# Dartautomat.net
KiCad netlist of a schematic drawn in EAGLE
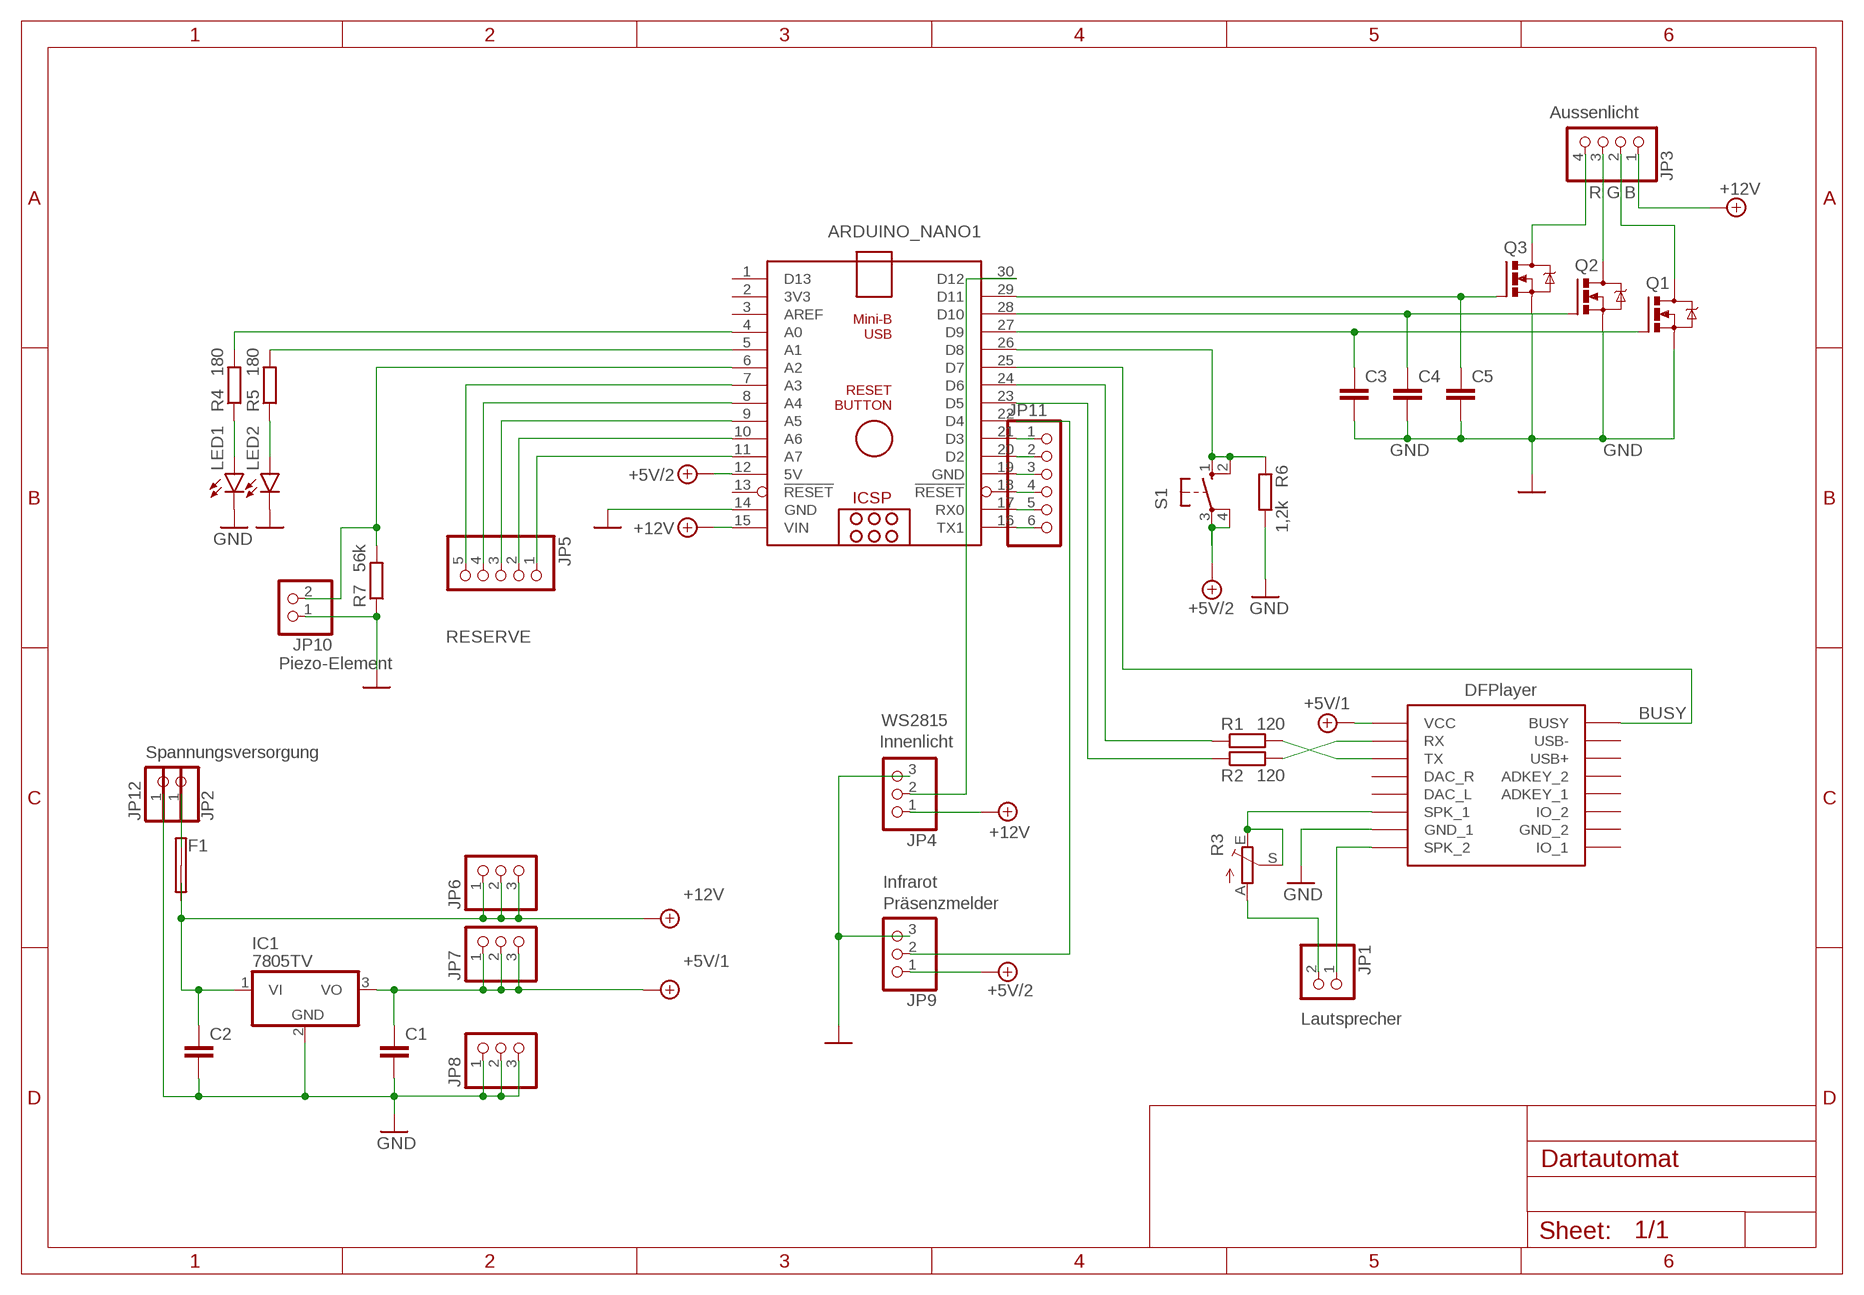
[diagram p0: schematic, sheet 1]

(export (version "E")
  (design (tool "Eeschema 10.0.6"))
  (components
    (comp (ref "ARDUINO_NANO1")
      (value "ARDUINO_NANO")
      (footprint "eagle-import:ARDUINO_NANO")
      (libsource (lib "eagle-import") (part "ARDUINO_NANO"))
    )
    (comp (ref "C1")
      (value "C-EU050-045X075")
      (footprint "eagle-import:C050-045X075")
      (libsource (lib "eagle-import") (part "C-EU050-045X075"))
    )
    (comp (ref "C2")
      (value "C-EU050-045X075")
      (footprint "eagle-import:C050-045X075")
      (libsource (lib "eagle-import") (part "C-EU050-045X075"))
    )
    (comp (ref "C3")
      (value "C-EU050-045X075")
      (footprint "eagle-import:C050-045X075")
      (libsource (lib "eagle-import") (part "C-EU050-045X075"))
    )
    (comp (ref "C4")
      (value "C-EU050-045X075")
      (footprint "eagle-import:C050-045X075")
      (libsource (lib "eagle-import") (part "C-EU050-045X075"))
    )
    (comp (ref "C5")
      (value "C-EU050-045X075")
      (footprint "eagle-import:C050-045X075")
      (libsource (lib "eagle-import") (part "C-EU050-045X075"))
    )
    (comp (ref "F1")
      (value "SHK20L")
      (footprint "eagle-import:SHK20L")
      (libsource (lib "eagle-import") (part "SHK20L"))
    )
    (comp (ref "IC1")
      (value "7805TV")
      (footprint "eagle-import:TO220V")
      (libsource (lib "eagle-import") (part "78TV05"))
    )
    (comp (ref "JP1")
      (value "PINHD-1X2")
      (footprint "eagle-import:1X02")
      (libsource (lib "eagle-import") (part "PINHD-1X2"))
    )
    (comp (ref "JP2")
      (value "PINHD-1X1")
      (footprint "eagle-import:1X01")
      (libsource (lib "eagle-import") (part "PINHD-1X1"))
    )
    (comp (ref "JP3")
      (value "PINHD-1X4")
      (footprint "eagle-import:1X04")
      (libsource (lib "eagle-import") (part "PINHD-1X4"))
    )
    (comp (ref "JP4")
      (value "PINHD-1X3")
      (footprint "eagle-import:1X03")
      (libsource (lib "eagle-import") (part "PINHD-1X3"))
    )
    (comp (ref "JP5")
      (value "PINHD-1X5")
      (footprint "eagle-import:1X05")
      (libsource (lib "eagle-import") (part "PINHD-1X5"))
    )
    (comp (ref "JP6")
      (value "PINHD-1X3")
      (footprint "eagle-import:1X03")
      (libsource (lib "eagle-import") (part "PINHD-1X3"))
    )
    (comp (ref "JP7")
      (value "PINHD-1X3")
      (footprint "eagle-import:1X03")
      (libsource (lib "eagle-import") (part "PINHD-1X3"))
    )
    (comp (ref "JP8")
      (value "PINHD-1X3")
      (footprint "eagle-import:1X03")
      (libsource (lib "eagle-import") (part "PINHD-1X3"))
    )
    (comp (ref "JP9")
      (value "PINHD-1X3")
      (footprint "eagle-import:1X03")
      (libsource (lib "eagle-import") (part "PINHD-1X3"))
    )
    (comp (ref "JP10")
      (value "PINHD-1X2")
      (footprint "eagle-import:1X02")
      (libsource (lib "eagle-import") (part "PINHD-1X2"))
    )
    (comp (ref "JP11")
      (value "PINHD-1X6")
      (footprint "eagle-import:1X06")
      (libsource (lib "eagle-import") (part "PINHD-1X6"))
    )
    (comp (ref "JP12")
      (value "PINHD-1X1")
      (footprint "eagle-import:1X01")
      (libsource (lib "eagle-import") (part "PINHD-1X1"))
    )
    (comp (ref "LED1")
      (value "LED3MM")
      (footprint "eagle-import:LED3MM")
      (libsource (lib "eagle-import") (part "LED3MM"))
    )
    (comp (ref "LED2")
      (value "LED3MM")
      (footprint "eagle-import:LED3MM")
      (libsource (lib "eagle-import") (part "LED3MM"))
    )
    (comp (ref "Q1")
      (value "IRLZ44ZNEU")
      (footprint "eagle-import:TO220BV")
      (libsource (lib "eagle-import") (part "IRLZ44ZNEU"))
    )
    (comp (ref "Q2")
      (value "IRLZ44ZNEU")
      (footprint "eagle-import:TO220BV")
      (libsource (lib "eagle-import") (part "IRLZ44ZNEU"))
    )
    (comp (ref "Q3")
      (value "IRLZ44ZNEU")
      (footprint "eagle-import:TO220BV")
      (libsource (lib "eagle-import") (part "IRLZ44ZNEU"))
    )
    (comp (ref "R1")
      (value "120")
      (footprint "eagle-import:0207_10")
      (libsource (lib "eagle-import") (part "R-EU_0207/10"))
    )
    (comp (ref "R2")
      (value "120")
      (footprint "eagle-import:0207_10")
      (libsource (lib "eagle-import") (part "R-EU_0207/10"))
    )
    (comp (ref "R3")
      (value "TRIM_EU-CA6H")
      (footprint "eagle-import:CA6H")
      (libsource (lib "eagle-import") (part "TRIM_EU-CA6H"))
    )
    (comp (ref "R4")
      (value "180")
      (footprint "eagle-import:0207_12")
      (libsource (lib "eagle-import") (part "R-EU_0207/12"))
    )
    (comp (ref "R5")
      (value "180")
      (footprint "eagle-import:0207_12")
      (libsource (lib "eagle-import") (part "R-EU_0207/12"))
    )
    (comp (ref "R6")
      (value "1,2k")
      (footprint "eagle-import:0207_12")
      (libsource (lib "eagle-import") (part "R-EU_0207/12"))
    )
    (comp (ref "R7")
      (value "56k")
      (footprint "eagle-import:0207_12")
      (libsource (lib "eagle-import") (part "R-EU_0207/12"))
    )
    (comp (ref "S1")
      (value "10-XX")
      (footprint "eagle-import:B3F-10XX")
      (fields (field (name "MPN") "B3F-1000"))
      (libsource (lib "eagle-import") (part "10-XX"))
    )
    (comp (ref "U$1")
      (value "DFPLAYER")
      (footprint "eagle-import:DFPLAYER")
      (libsource (lib "eagle-import") (part "DFPLAYER"))
    )
  )
  (nets
    (net (code "1") (name "+5V{slash}1") (class "Default")
      (node (ref "C1") (pin "1") (pinfunction "1_1") (pintype "passive"))
      (node (ref "IC1") (pin "3") (pinfunction "VO_3") (pintype "passive"))
      (node (ref "JP7") (pin "1") (pinfunction "1_1") (pintype "passive"))
      (node (ref "JP7") (pin "2") (pinfunction "2_2") (pintype "passive"))
      (node (ref "JP7") (pin "3") (pinfunction "3_3") (pintype "passive"))
      (node (ref "U$1") (pin "VCC") (pinfunction "VCC_VCC") (pintype "bidirectional"))
    )
    (net (code "2") (name "+5V{slash}2") (class "Default")
      (node (ref "ARDUINO_NANO1") (pin "12") (pinfunction "5V_12") (pintype "power_in"))
      (node (ref "JP9") (pin "1") (pinfunction "1_1") (pintype "passive"))
      (node (ref "S1") (pin "3") (pinfunction "P_3") (pintype "passive"))
      (node (ref "S1") (pin "4") (pinfunction "P1_4") (pintype "passive"))
    )
    (net (code "3") (name "+12V") (class "Default")
      (node (ref "ARDUINO_NANO1") (pin "15") (pinfunction "VIN_15") (pintype "power_in"))
      (node (ref "C2") (pin "1") (pinfunction "1_1") (pintype "passive"))
      (node (ref "F1") (pin "1A") (pinfunction "1A_1A") (pintype "passive"))
      (node (ref "F1") (pin "1B") (pinfunction "1B_1B") (pintype "passive"))
      (node (ref "IC1") (pin "1") (pinfunction "VI_1") (pintype "input"))
      (node (ref "JP3") (pin "1") (pinfunction "1_1") (pintype "passive"))
      (node (ref "JP4") (pin "1") (pinfunction "1_1") (pintype "passive"))
      (node (ref "JP6") (pin "1") (pinfunction "1_1") (pintype "passive"))
      (node (ref "JP6") (pin "2") (pinfunction "2_2") (pintype "passive"))
      (node (ref "JP6") (pin "3") (pinfunction "3_3") (pintype "passive"))
    )
    (net (code "4") (name "/BUSY") (class "Default")
      (node (ref "ARDUINO_NANO1") (pin "25") (pinfunction "D7_25") (pintype "bidirectional"))
      (node (ref "U$1") (pin "BUSY") (pinfunction "BUSY_BUSY") (pintype "bidirectional"))
    )
    (net (code "5") (name "GND") (class "Default")
      (node (ref "ARDUINO_NANO1") (pin "14") (pinfunction "GND_14") (pintype "power_in"))
      (node (ref "C1") (pin "2") (pinfunction "2_2") (pintype "passive"))
      (node (ref "C2") (pin "2") (pinfunction "2_2") (pintype "passive"))
      (node (ref "C3") (pin "2") (pinfunction "2_2") (pintype "passive"))
      (node (ref "C4") (pin "2") (pinfunction "2_2") (pintype "passive"))
      (node (ref "C5") (pin "2") (pinfunction "2_2") (pintype "passive"))
      (node (ref "IC1") (pin "2") (pinfunction "GND_2") (pintype "passive"))
      (node (ref "JP10") (pin "1") (pinfunction "1_1") (pintype "passive"))
      (node (ref "JP12") (pin "1") (pinfunction "1_1") (pintype "passive"))
      (node (ref "JP4") (pin "3") (pinfunction "3_3") (pintype "passive"))
      (node (ref "JP8") (pin "1") (pinfunction "1_1") (pintype "passive"))
      (node (ref "JP8") (pin "2") (pinfunction "2_2") (pintype "passive"))
      (node (ref "JP8") (pin "3") (pinfunction "3_3") (pintype "passive"))
      (node (ref "JP9") (pin "3") (pinfunction "3_3") (pintype "passive"))
      (node (ref "LED1") (pin "K") (pinfunction "C_K") (pintype "passive"))
      (node (ref "LED2") (pin "K") (pinfunction "C_K") (pintype "passive"))
      (node (ref "Q1") (pin "S") (pinfunction "S_S") (pintype "passive"))
      (node (ref "Q2") (pin "S") (pinfunction "S_S") (pintype "passive"))
      (node (ref "Q3") (pin "S") (pinfunction "S_S") (pintype "passive"))
      (node (ref "R6") (pin "2") (pinfunction "2_2") (pintype "passive"))
      (node (ref "R7") (pin "1") (pinfunction "1_1") (pintype "passive"))
      (node (ref "U$1") (pin "GND_1") (pinfunction "GND_1_GND_1") (pintype "bidirectional"))
    )
    (net (code "6") (name "Net-(ARDUINO_NANO1-A0)") (class "Default")
      (node (ref "ARDUINO_NANO1") (pin "4") (pinfunction "A0_4") (pintype "bidirectional"))
      (node (ref "R4") (pin "2") (pinfunction "2_2") (pintype "passive"))
    )
    (net (code "7") (name "Net-(ARDUINO_NANO1-A1)") (class "Default")
      (node (ref "ARDUINO_NANO1") (pin "5") (pinfunction "A1_5") (pintype "bidirectional"))
      (node (ref "R5") (pin "2") (pinfunction "2_2") (pintype "passive"))
    )
    (net (code "8") (name "Net-(ARDUINO_NANO1-A2)") (class "Default")
      (node (ref "ARDUINO_NANO1") (pin "6") (pinfunction "A2_6") (pintype "bidirectional"))
      (node (ref "JP10") (pin "2") (pinfunction "2_2") (pintype "passive"))
      (node (ref "R7") (pin "2") (pinfunction "2_2") (pintype "passive"))
    )
    (net (code "9") (name "Net-(ARDUINO_NANO1-A3)") (class "Default")
      (node (ref "ARDUINO_NANO1") (pin "7") (pinfunction "A3_7") (pintype "bidirectional"))
      (node (ref "JP5") (pin "5") (pinfunction "5_5") (pintype "passive"))
    )
    (net (code "10") (name "Net-(ARDUINO_NANO1-A4)") (class "Default")
      (node (ref "ARDUINO_NANO1") (pin "8") (pinfunction "A4_8") (pintype "bidirectional"))
      (node (ref "JP5") (pin "4") (pinfunction "4_4") (pintype "passive"))
    )
    (net (code "11") (name "Net-(ARDUINO_NANO1-A5)") (class "Default")
      (node (ref "ARDUINO_NANO1") (pin "9") (pinfunction "A5_9") (pintype "bidirectional"))
      (node (ref "JP5") (pin "3") (pinfunction "3_3") (pintype "passive"))
    )
    (net (code "12") (name "Net-(ARDUINO_NANO1-A6)") (class "Default")
      (node (ref "ARDUINO_NANO1") (pin "10") (pinfunction "A6_10") (pintype "bidirectional"))
      (node (ref "JP5") (pin "2") (pinfunction "2_2") (pintype "passive"))
    )
    (net (code "13") (name "Net-(ARDUINO_NANO1-A7)") (class "Default")
      (node (ref "ARDUINO_NANO1") (pin "11") (pinfunction "A7_11") (pintype "bidirectional"))
      (node (ref "JP5") (pin "1") (pinfunction "1_1") (pintype "passive"))
    )
    (net (code "14") (name "Net-(ARDUINO_NANO1-D2)") (class "Default")
      (node (ref "ARDUINO_NANO1") (pin "20") (pinfunction "D2_20") (pintype "bidirectional"))
      (node (ref "JP11") (pin "2") (pinfunction "2_2") (pintype "passive"))
    )
    (net (code "15") (name "Net-(ARDUINO_NANO1-D3)") (class "Default")
      (node (ref "ARDUINO_NANO1") (pin "21") (pinfunction "D3_21") (pintype "bidirectional"))
      (node (ref "JP11") (pin "1") (pinfunction "1_1") (pintype "passive"))
    )
    (net (code "16") (name "Net-(ARDUINO_NANO1-D4)") (class "Default")
      (node (ref "ARDUINO_NANO1") (pin "22") (pinfunction "D4_22") (pintype "bidirectional"))
      (node (ref "JP9") (pin "2") (pinfunction "2_2") (pintype "passive"))
    )
    (net (code "17") (name "Net-(ARDUINO_NANO1-D5)") (class "Default")
      (node (ref "ARDUINO_NANO1") (pin "23") (pinfunction "D5_23") (pintype "bidirectional"))
      (node (ref "R2") (pin "1") (pinfunction "1_1") (pintype "passive"))
    )
    (net (code "18") (name "Net-(ARDUINO_NANO1-D6)") (class "Default")
      (node (ref "ARDUINO_NANO1") (pin "24") (pinfunction "D6_24") (pintype "bidirectional"))
      (node (ref "R1") (pin "1") (pinfunction "1_1") (pintype "passive"))
    )
    (net (code "19") (name "Net-(ARDUINO_NANO1-D8)") (class "Default")
      (node (ref "ARDUINO_NANO1") (pin "26") (pinfunction "D8_26") (pintype "bidirectional"))
      (node (ref "R6") (pin "1") (pinfunction "1_1") (pintype "passive"))
      (node (ref "S1") (pin "1") (pinfunction "S_1") (pintype "passive"))
      (node (ref "S1") (pin "2") (pinfunction "S1_2") (pintype "passive"))
    )
    (net (code "20") (name "Net-(ARDUINO_NANO1-D9)") (class "Default")
      (node (ref "ARDUINO_NANO1") (pin "27") (pinfunction "D9_27") (pintype "bidirectional"))
      (node (ref "C3") (pin "1") (pinfunction "1_1") (pintype "passive"))
      (node (ref "Q1") (pin "G") (pinfunction "G_G") (pintype "passive"))
    )
    (net (code "21") (name "Net-(ARDUINO_NANO1-D10)") (class "Default")
      (node (ref "ARDUINO_NANO1") (pin "28") (pinfunction "D10_28") (pintype "bidirectional"))
      (node (ref "C4") (pin "1") (pinfunction "1_1") (pintype "passive"))
      (node (ref "Q2") (pin "G") (pinfunction "G_G") (pintype "passive"))
    )
    (net (code "22") (name "Net-(ARDUINO_NANO1-D11)") (class "Default")
      (node (ref "ARDUINO_NANO1") (pin "29") (pinfunction "D11_29") (pintype "bidirectional"))
      (node (ref "C5") (pin "1") (pinfunction "1_1") (pintype "passive"))
      (node (ref "Q3") (pin "G") (pinfunction "G_G") (pintype "passive"))
    )
    (net (code "23") (name "Net-(ARDUINO_NANO1-D12)") (class "Default")
      (node (ref "ARDUINO_NANO1") (pin "30") (pinfunction "D12_30") (pintype "bidirectional"))
      (node (ref "JP4") (pin "2") (pinfunction "2_2") (pintype "passive"))
    )
    (net (code "24") (name "Net-(ARDUINO_NANO1-GND-Pad19)") (class "Default")
      (node (ref "ARDUINO_NANO1") (pin "19") (pinfunction "GND_19") (pintype "power_in"))
      (node (ref "JP11") (pin "3") (pinfunction "3_3") (pintype "passive"))
    )
    (net (code "25") (name "Net-(ARDUINO_NANO1-RX0)") (class "Default")
      (node (ref "ARDUINO_NANO1") (pin "17") (pinfunction "RX0_17") (pintype "bidirectional"))
      (node (ref "JP11") (pin "5") (pinfunction "5_5") (pintype "passive"))
    )
    (net (code "26") (name "Net-(ARDUINO_NANO1-TX1)") (class "Default")
      (node (ref "ARDUINO_NANO1") (pin "16") (pinfunction "TX1_16") (pintype "bidirectional"))
      (node (ref "JP11") (pin "6") (pinfunction "6_6") (pintype "passive"))
    )
    (net (code "27") (name "Net-(ARDUINO_NANO1-~{RESET}-Pad18)") (class "Default")
      (node (ref "ARDUINO_NANO1") (pin "18") (pinfunction "~{RESET}_18") (pintype "input"))
      (node (ref "JP11") (pin "4") (pinfunction "4_4") (pintype "passive"))
    )
    (net (code "28") (name "Net-(F1-Pad2A)") (class "Default")
      (node (ref "F1") (pin "2A") (pinfunction "2A_2A") (pintype "passive"))
      (node (ref "F1") (pin "2B") (pinfunction "2B_2B") (pintype "passive"))
      (node (ref "JP2") (pin "1") (pinfunction "1_1") (pintype "passive"))
    )
    (net (code "29") (name "Net-(JP1-Pad2)") (class "Default")
      (node (ref "JP1") (pin "2") (pinfunction "2_2") (pintype "passive"))
      (node (ref "R3") (pin "A") (pinfunction "A_A") (pintype "passive"))
    )
    (net (code "30") (name "Net-(JP3-Pad2)") (class "Default")
      (node (ref "JP3") (pin "2") (pinfunction "2_2") (pintype "passive"))
      (node (ref "Q1") (pin "D") (pinfunction "D_D") (pintype "passive"))
    )
    (net (code "31") (name "Net-(JP3-Pad3)") (class "Default")
      (node (ref "JP3") (pin "3") (pinfunction "3_3") (pintype "passive"))
      (node (ref "Q2") (pin "D") (pinfunction "D_D") (pintype "passive"))
    )
    (net (code "32") (name "Net-(JP3-Pad4)") (class "Default")
      (node (ref "JP3") (pin "4") (pinfunction "4_4") (pintype "passive"))
      (node (ref "Q3") (pin "D") (pinfunction "D_D") (pintype "passive"))
    )
    (net (code "33") (name "Net-(LED1-PadA)") (class "Default")
      (node (ref "LED1") (pin "A") (pinfunction "A_A") (pintype "passive"))
      (node (ref "R4") (pin "1") (pinfunction "1_1") (pintype "passive"))
    )
    (net (code "34") (name "Net-(LED2-PadA)") (class "Default")
      (node (ref "LED2") (pin "A") (pinfunction "A_A") (pintype "passive"))
      (node (ref "R5") (pin "1") (pinfunction "1_1") (pintype "passive"))
    )
    (net (code "35") (name "Net-(R1-Pad2)") (class "Default")
      (node (ref "R1") (pin "2") (pinfunction "2_2") (pintype "passive"))
      (node (ref "U$1") (pin "TX") (pinfunction "TX_TX") (pintype "bidirectional"))
    )
    (net (code "36") (name "Net-(R2-Pad2)") (class "Default")
      (node (ref "R2") (pin "2") (pinfunction "2_2") (pintype "passive"))
      (node (ref "U$1") (pin "RX") (pinfunction "RX_RX") (pintype "bidirectional"))
    )
    (net (code "37") (name "Net-(U$1-SPK_1)") (class "Default")
      (node (ref "R3") (pin "E") (pinfunction "E_E") (pintype "passive"))
      (node (ref "R3") (pin "S") (pinfunction "S_S") (pintype "passive"))
      (node (ref "U$1") (pin "SPK1") (pinfunction "SPK_1_SPK1") (pintype "bidirectional"))
    )
    (net (code "38") (name "Net-(U$1-SPK_2)") (class "Default")
      (node (ref "JP1") (pin "1") (pinfunction "1_1") (pintype "passive"))
      (node (ref "U$1") (pin "SPK2") (pinfunction "SPK_2_SPK2") (pintype "bidirectional"))
    )
    (net (code "39") (name "unconnected-(ARDUINO_NANO1-3V3-Pad2)") (class "Default")
      (node (ref "ARDUINO_NANO1") (pin "2") (pinfunction "3V3_2") (pintype "output"))
    )
    (net (code "40") (name "unconnected-(ARDUINO_NANO1-AREF-Pad3)") (class "Default")
      (node (ref "ARDUINO_NANO1") (pin "3") (pinfunction "AREF_3") (pintype "input"))
    )
    (net (code "41") (name "unconnected-(ARDUINO_NANO1-D13-Pad1)") (class "Default")
      (node (ref "ARDUINO_NANO1") (pin "1") (pinfunction "D13_1") (pintype "bidirectional"))
    )
    (net (code "42") (name "unconnected-(ARDUINO_NANO1-~{RESET}-Pad13)") (class "Default")
      (node (ref "ARDUINO_NANO1") (pin "13") (pinfunction "~{RESET}_13") (pintype "input"))
    )
    (net (code "43") (name "unconnected-(U$1-ADKEY_1-PadADKEY1)") (class "Default")
      (node (ref "U$1") (pin "ADKEY1") (pinfunction "ADKEY_1_ADKEY1") (pintype "bidirectional"))
    )
    (net (code "44") (name "unconnected-(U$1-ADKEY_2-PadADKEY2)") (class "Default")
      (node (ref "U$1") (pin "ADKEY2") (pinfunction "ADKEY_2_ADKEY2") (pintype "bidirectional"))
    )
    (net (code "45") (name "unconnected-(U$1-IO_1-PadIO1)") (class "Default")
      (node (ref "U$1") (pin "IO1") (pinfunction "IO_1_IO1") (pintype "bidirectional"))
    )
    (net (code "46") (name "unconnected-(U$1-IO_2-PadIO2)") (class "Default")
      (node (ref "U$1") (pin "IO2") (pinfunction "IO_2_IO2") (pintype "bidirectional"))
    )
    (net (code "47") (name "unconnected-(U$1-PadDAC_L)") (class "Default")
      (node (ref "U$1") (pin "DAC_L") (pinfunction "DAC_L_DAC_L") (pintype "bidirectional"))
    )
    (net (code "48") (name "unconnected-(U$1-PadDAC_R)") (class "Default")
      (node (ref "U$1") (pin "DAC_R") (pinfunction "DAC_R_DAC_R") (pintype "bidirectional"))
    )
    (net (code "49") (name "unconnected-(U$1-PadGND_2)") (class "Default")
      (node (ref "U$1") (pin "GND_2") (pinfunction "GND_2_GND_2") (pintype "bidirectional"))
    )
    (net (code "50") (name "unconnected-(U$1-PadUSB+)") (class "Default")
      (node (ref "U$1") (pin "USB+") (pinfunction "USB+_USB+") (pintype "bidirectional"))
    )
    (net (code "51") (name "unconnected-(U$1-PadUSB-)") (class "Default")
      (node (ref "U$1") (pin "USB-") (pinfunction "USB-_USB-") (pintype "bidirectional"))
    )
  )
)
